# PIR_MotionDetector.net
KiCad netlist of a schematic drawn in EAGLE
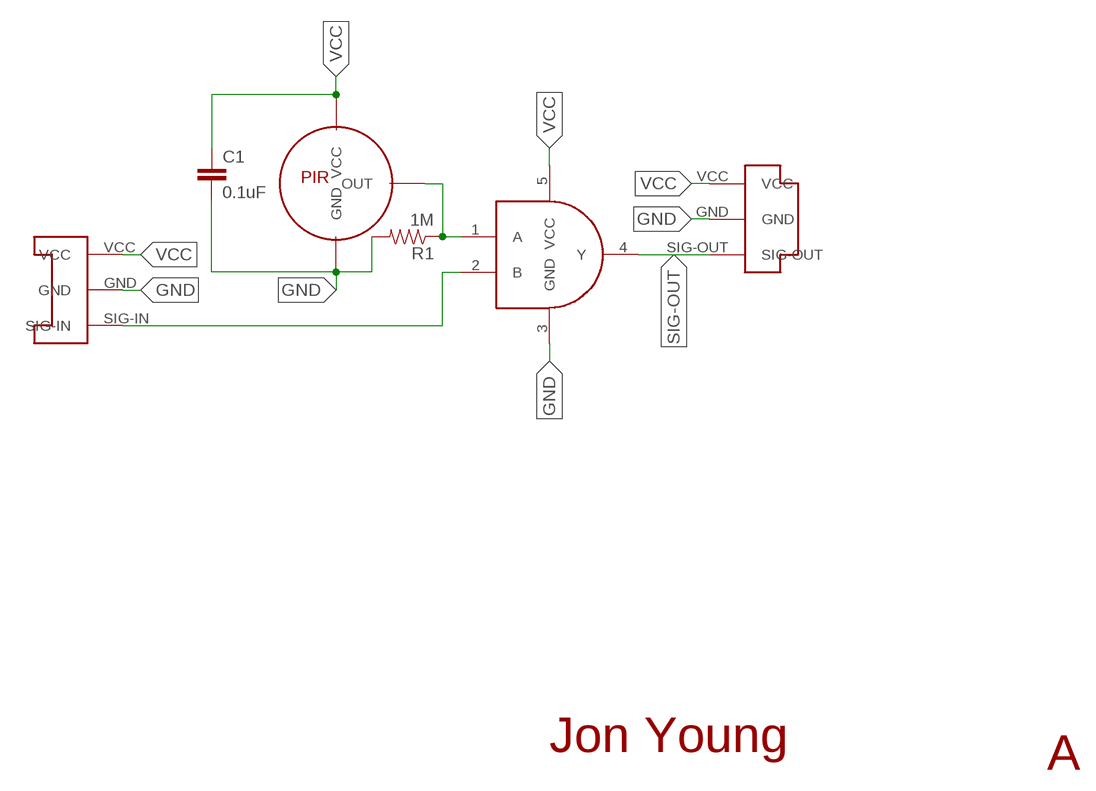
[diagram p0: schematic, sheet 1]

(export (version "E")
  (design (tool "Eeschema 10.0.6"))
  (components
    (comp (ref "C1")
      (value "0.1uF")
      (footprint "eagle-import:0603-CAP")
      (libsource (lib "eagle-import") (part "CAP0603-CAP"))
    )
    (comp (ref "R1")
      (value "1M")
      (footprint "eagle-import:0603-RES")
      (libsource (lib "eagle-import") (part "1MOHM-1/10W-1%(0603)"))
    )
    (comp (ref "U$1")
      (value "CONN-PLUG-3POS-3MM")
      (footprint "eagle-import:PLUG-3POS-3MM-SMD")
      (libsource (lib "eagle-import") (part "CONN-PLUG-3POS-3MM"))
    )
    (comp (ref "U$2")
      (value "CONN-SOCKET-3POS-3MM")
      (footprint "eagle-import:SOCKET-3POS-3MM-SMD")
      (libsource (lib "eagle-import") (part "CONN-SOCKET-3POS-3MM"))
    )
    (comp (ref "U$3")
      (value "PIR-PANASONIC-WL")
      (footprint "eagle-import:TO-5-3PIN")
      (libsource (lib "eagle-import") (part "PIR-PANASONIC-WL"))
    )
    (comp (ref "U$4")
      (value "AND-NC7SZ08")
      (footprint "eagle-import:SC70")
      (libsource (lib "eagle-import") (part "AND-NC7SZ08"))
    )
  )
  (nets
    (net (code "1") (name "GND") (class "Default")
      (node (ref "C1") (pin "2") (pinfunction "2_2") (pintype "passive"))
      (node (ref "R1") (pin "2") (pinfunction "2_2") (pintype "passive"))
      (node (ref "U$1") (pin "GND") (pinfunction "GND_GND") (pintype "power_in"))
      (node (ref "U$2") (pin "GND") (pinfunction "GND_GND") (pintype "power_in"))
      (node (ref "U$3") (pin "GND") (pinfunction "GND_GND") (pintype "power_in"))
      (node (ref "U$4") (pin "3") (pinfunction "GND_3") (pintype "power_in"))
    )
    (net (code "2") (name "Net-(U$4-A)") (class "Default")
      (node (ref "R1") (pin "1") (pinfunction "1_1") (pintype "passive"))
      (node (ref "U$3") (pin "OUT") (pinfunction "OUT_OUT") (pintype "output"))
      (node (ref "U$4") (pin "1") (pinfunction "A_1") (pintype "input"))
    )
    (net (code "3") (name "Net-(U$4-B)") (class "Default")
      (node (ref "U$2") (pin "SIG-IN") (pinfunction "SIG-IN_SIG-IN") (pintype "bidirectional"))
      (node (ref "U$4") (pin "2") (pinfunction "B_2") (pintype "input"))
    )
    (net (code "4") (name "SIG-OUT") (class "Default")
      (node (ref "U$1") (pin "SIG-OUT") (pinfunction "SIG-OUT_SIG-OUT") (pintype "bidirectional"))
      (node (ref "U$4") (pin "4") (pinfunction "Y_4") (pintype "output"))
    )
    (net (code "5") (name "VCC") (class "Default")
      (node (ref "C1") (pin "1") (pinfunction "1_1") (pintype "passive"))
      (node (ref "U$1") (pin "VCC") (pinfunction "VCC_VCC") (pintype "power_in"))
      (node (ref "U$2") (pin "VCC") (pinfunction "VCC_VCC") (pintype "power_in"))
      (node (ref "U$3") (pin "VCC") (pinfunction "VCC_VCC") (pintype "power_in"))
      (node (ref "U$4") (pin "5") (pinfunction "VCC_5") (pintype "power_in"))
    )
  )
)
